# snare.net
KiCad netlist of a schematic drawn in EAGLE
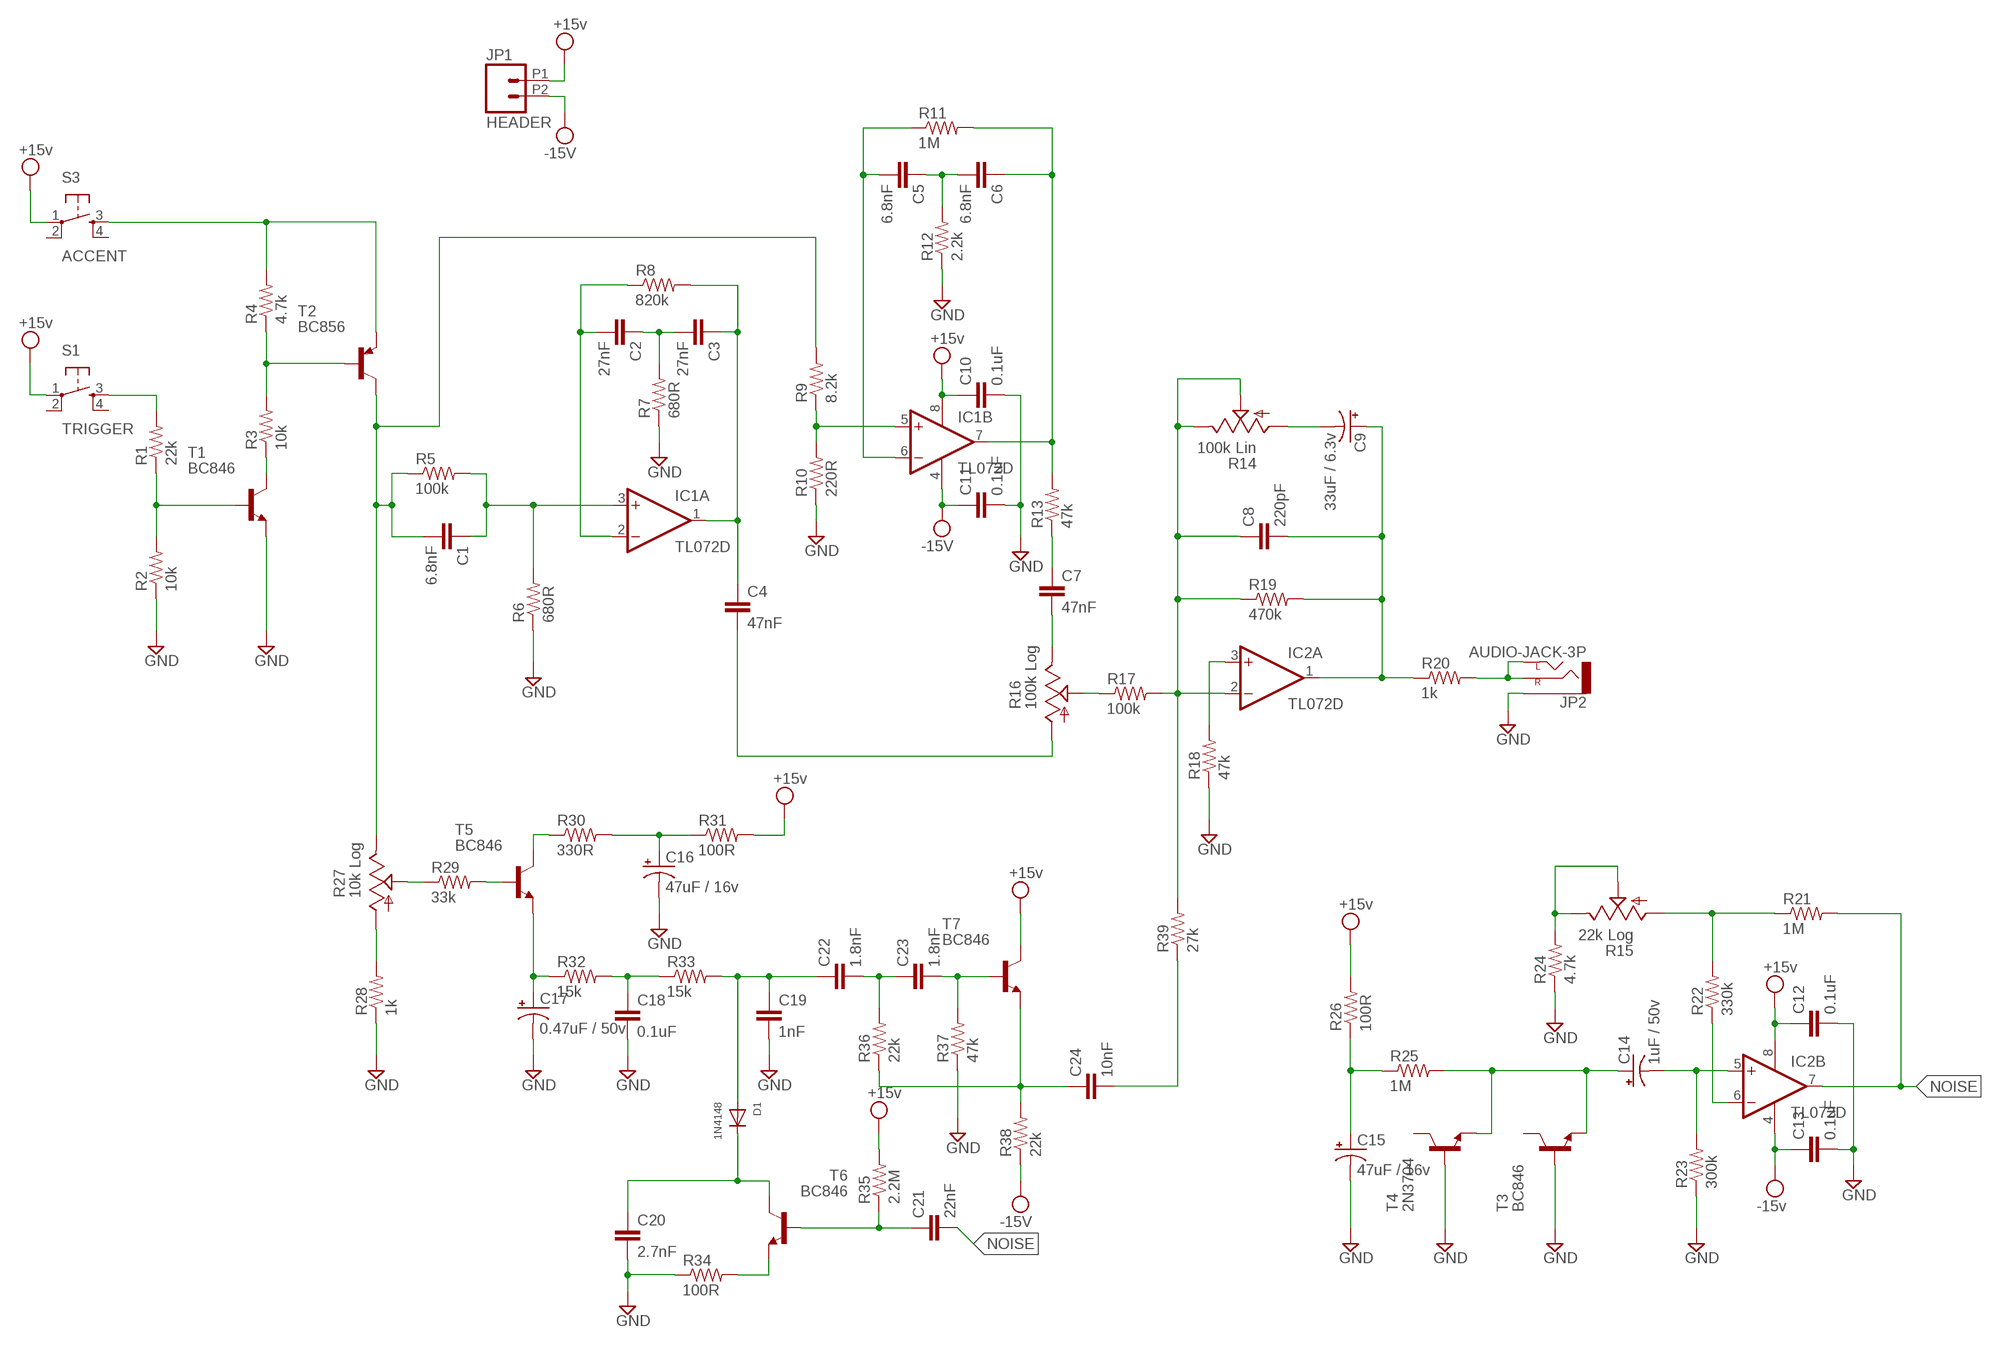
[diagram p0: schematic, sheet 1]

(export (version "E")
  (design (tool "Eeschema 10.0.6"))
  (components
    (comp (ref "C1")
      (value "6.8nF")
      (footprint "eagle-import:0805")
      (fields (field (name "PARTNO") "C0805C682K5RACTU"))
      (libsource (lib "eagle-import") (part "CAP0805"))
    )
    (comp (ref "C2")
      (value "27nF")
      (footprint "eagle-import:0805")
      (fields (field (name "PARTNO") "CC0805KRX7R9BB273"))
      (libsource (lib "eagle-import") (part "CAP0805"))
    )
    (comp (ref "C3")
      (value "27nF")
      (footprint "eagle-import:0805")
      (fields (field (name "PARTNO") "CC0805KRX7R9BB273"))
      (libsource (lib "eagle-import") (part "CAP0805"))
    )
    (comp (ref "C4")
      (value "47nF")
      (footprint "eagle-import:0805")
      (fields (field (name "PARTNO") "C0805C473K5RACTU"))
      (libsource (lib "eagle-import") (part "CAP0805"))
    )
    (comp (ref "C5")
      (value "6.8nF")
      (footprint "eagle-import:0805")
      (fields (field (name "PARTNO") "C0805C682K5RACTU"))
      (libsource (lib "eagle-import") (part "CAP0805"))
    )
    (comp (ref "C6")
      (value "6.8nF")
      (footprint "eagle-import:0805")
      (fields (field (name "PARTNO") "C0805C682K5RACTU"))
      (libsource (lib "eagle-import") (part "CAP0805"))
    )
    (comp (ref "C7")
      (value "47nF")
      (footprint "eagle-import:0805")
      (fields (field (name "PARTNO") "C0805C473K5RACTU"))
      (libsource (lib "eagle-import") (part "CAP0805"))
    )
    (comp (ref "C8")
      (value "220pF")
      (footprint "eagle-import:0805")
      (fields (field (name "PARTNO") "CC0805KRX7R9BB221"))
      (libsource (lib "eagle-import") (part "CAP0805"))
    )
    (comp (ref "C9")
      (value "33uF / 6.3v")
      (footprint "eagle-import:PANASONIC_VS_B-2")
      (fields (field (name "PARTNO") "EEE-1AA330WAR"))
      (libsource (lib "eagle-import") (part "CAP-POLPANASONIC_B-2"))
    )
    (comp (ref "C10")
      (value "0.1uF")
      (footprint "eagle-import:0805")
      (fields (field (name "PARTNO") "C0805C104K5RACTU"))
      (libsource (lib "eagle-import") (part "CAP0805"))
    )
    (comp (ref "C11")
      (value "0.1uF")
      (footprint "eagle-import:0805")
      (fields (field (name "PARTNO") "C0805C104K5RACTU"))
      (libsource (lib "eagle-import") (part "CAP0805"))
    )
    (comp (ref "C12")
      (value "0.1uF")
      (footprint "eagle-import:0805")
      (fields (field (name "PARTNO") "C0805C104K5RACTU"))
      (libsource (lib "eagle-import") (part "CAP0805"))
    )
    (comp (ref "C13")
      (value "0.1uF")
      (footprint "eagle-import:0805")
      (fields (field (name "PARTNO") "C0805C104K5RACTU"))
      (libsource (lib "eagle-import") (part "CAP0805"))
    )
    (comp (ref "C14")
      (value "1uF / 50v")
      (footprint "eagle-import:PANASONIC_VS_B-2")
      (fields (field (name "PARTNO") "EEE-1HA010SR"))
      (libsource (lib "eagle-import") (part "CAP-POLPANASONIC_B-2"))
    )
    (comp (ref "C15")
      (value "47uF / 16v")
      (footprint "eagle-import:PANASONIC_VS_B-2")
      (fields (field (name "PARTNO") "EEE-1HAR47AR"))
      (libsource (lib "eagle-import") (part "CAP-POLPANASONIC_B-2"))
    )
    (comp (ref "C16")
      (value "47uF / 16v")
      (footprint "eagle-import:PANASONIC_VS_B-2")
      (fields (field (name "PARTNO") "EEE-1HAR47AR"))
      (libsource (lib "eagle-import") (part "CAP-POLPANASONIC_B-2"))
    )
    (comp (ref "C17")
      (value "0.47uF / 50v")
      (footprint "eagle-import:PANASONIC_VS_B-2")
      (fields (field (name "PARTNO") "EEE-1HAR47AR"))
      (libsource (lib "eagle-import") (part "CAP-POLPANASONIC_B-2"))
    )
    (comp (ref "C18")
      (value "0.1uF")
      (footprint "eagle-import:0805")
      (fields (field (name "PARTNO") "C0805C104K5RACTU"))
      (libsource (lib "eagle-import") (part "CAP0805"))
    )
    (comp (ref "C19")
      (value "1nF")
      (footprint "eagle-import:0805")
      (fields (field (name "PARTNO") "C0805C102K5RACTU"))
      (libsource (lib "eagle-import") (part "CAP0805"))
    )
    (comp (ref "C20")
      (value "2.7nF")
      (footprint "eagle-import:0805")
      (fields (field (name "PARTNO") "CC0805KRX7R9BB272"))
      (libsource (lib "eagle-import") (part "CAP0805"))
    )
    (comp (ref "C21")
      (value "22nF")
      (footprint "eagle-import:0805")
      (fields (field (name "PARTNO") "CL21B223KBANNNC"))
      (libsource (lib "eagle-import") (part "CAP0805"))
    )
    (comp (ref "C22")
      (value "1.8nF")
      (footprint "eagle-import:0805")
      (fields (field (name "PARTNO") "08055C182KAT2A"))
      (libsource (lib "eagle-import") (part "CAP0805"))
    )
    (comp (ref "C23")
      (value "1.8nF")
      (footprint "eagle-import:0805")
      (fields (field (name "PARTNO") "08055C182KAT2A"))
      (libsource (lib "eagle-import") (part "CAP0805"))
    )
    (comp (ref "C24")
      (value "10nF")
      (footprint "eagle-import:0805")
      (fields (field (name "PARTNO") "GRM216R71H103KA01D"))
      (libsource (lib "eagle-import") (part "CAP0805"))
    )
    (comp (ref "D1")
      (value "1N4148")
      (footprint "eagle-import:SOD-323F")
      (fields (field (name "PARTNO") "1N4148WS"))
      (libsource (lib "eagle-import") (part "DIODESOD-323F"))
    )
    (comp (ref "IC1")
      (value "TL072D")
      (footprint "eagle-import:SO08")
      (fields (field (name "PARTNO") "TL072SG-13"))
      (libsource (lib "eagle-import") (part "TL072D"))
    )
    (comp (ref "IC2")
      (value "TL072D")
      (footprint "eagle-import:SO08")
      (fields (field (name "PARTNO") "TL072SG-13"))
      (libsource (lib "eagle-import") (part "TL072D"))
    )
    (comp (ref "JP1")
      (value "HEADER")
      (footprint "eagle-import:1X02-5.08-SCREWTERM")
      (libsource (lib "eagle-import") (part "HEADER"))
    )
    (comp (ref "JP2")
      (value "AUDIO-JACK-3P")
      (footprint "eagle-import:CUI-352X-SMT")
      (fields (field (name "PARTNO") "SJ-3523-SMT-TR"))
      (libsource (lib "eagle-import") (part "AUDIO-JACK-3P"))
    )
    (comp (ref "R1")
      (value "22k")
      (footprint "eagle-import:0805")
      (fields (field (name "PARTNO") "RMCF0805FT22K0"))
      (libsource (lib "eagle-import") (part "RESISTOR0805-RES"))
    )
    (comp (ref "R2")
      (value "10k")
      (footprint "eagle-import:0805")
      (fields (field (name "PARTNO") "RMCF0805FT10K0"))
      (libsource (lib "eagle-import") (part "RESISTOR0805-RES"))
    )
    (comp (ref "R3")
      (value "10k")
      (footprint "eagle-import:0805")
      (fields (field (name "PARTNO") "RMCF0805FT10K0"))
      (libsource (lib "eagle-import") (part "RESISTOR0805-RES"))
    )
    (comp (ref "R4")
      (value "4.7k")
      (footprint "eagle-import:0805")
      (fields (field (name "PARTNO") "RMCF0805FT4K70"))
      (libsource (lib "eagle-import") (part "RESISTOR0805-RES"))
    )
    (comp (ref "R5")
      (value "100k")
      (footprint "eagle-import:0805")
      (fields (field (name "PARTNO") "RMCF0805FT100K"))
      (libsource (lib "eagle-import") (part "RESISTOR0805-RES"))
    )
    (comp (ref "R6")
      (value "680R")
      (footprint "eagle-import:0805")
      (fields (field (name "PARTNO") "RMCF0805FT680R"))
      (libsource (lib "eagle-import") (part "RESISTOR0805-RES"))
    )
    (comp (ref "R7")
      (value "680R")
      (footprint "eagle-import:0805")
      (fields (field (name "PARTNO") "RMCF0805FT680R"))
      (libsource (lib "eagle-import") (part "RESISTOR0805-RES"))
    )
    (comp (ref "R8")
      (value "820k")
      (footprint "eagle-import:0805")
      (fields (field (name "PARTNO") "RC0805FR-07820KL"))
      (libsource (lib "eagle-import") (part "RESISTOR0805-RES"))
    )
    (comp (ref "R9")
      (value "8.2k")
      (footprint "eagle-import:0805")
      (fields (field (name "PARTNO") "RMCF0805FT8K20"))
      (libsource (lib "eagle-import") (part "RESISTOR0805-RES"))
    )
    (comp (ref "R10")
      (value "220R")
      (footprint "eagle-import:0805")
      (fields (field (name "PARTNO") "RMCF0805FT220R"))
      (libsource (lib "eagle-import") (part "RESISTOR0805-RES"))
    )
    (comp (ref "R11")
      (value "1M")
      (footprint "eagle-import:0805")
      (fields (field (name "PARTNO") "RMCF0805FT1M00"))
      (libsource (lib "eagle-import") (part "RESISTOR0805-RES"))
    )
    (comp (ref "R12")
      (value "2.2k")
      (footprint "eagle-import:0805")
      (fields (field (name "PARTNO") "RMCF0805FT2K20"))
      (libsource (lib "eagle-import") (part "RESISTOR0805-RES"))
    )
    (comp (ref "R13")
      (value "47k")
      (footprint "eagle-import:0805")
      (fields (field (name "PARTNO") "RMCF0805FT47K0"))
      (libsource (lib "eagle-import") (part "RESISTOR0805-RES"))
    )
    (comp (ref "R14")
      (value "100k Lin")
      (footprint "eagle-import:POTENTIOMETER-CTS296")
      (fields (field (name "PARTNO") "296UD104B1N"))
      (libsource (lib "eagle-import") (part "POTCTS296"))
    )
    (comp (ref "R15")
      (value "22k Log")
      (footprint "eagle-import:POTENTIOMETER-PTV09-HORIZ")
      (fields (field (name "PARTNO") "PTV09A-4025F-A203"))
      (libsource (lib "eagle-import") (part "POTPTV09-H"))
    )
    (comp (ref "R16")
      (value "100k Log")
      (footprint "eagle-import:POTENTIOMETER-PTV09-VERT")
      (fields (field (name "PARTNO") "PTV09A-2020F-A104"))
      (libsource (lib "eagle-import") (part "POTPTV09-V"))
    )
    (comp (ref "R17")
      (value "100k")
      (footprint "eagle-import:0805")
      (fields (field (name "PARTNO") "RMCF0805FT100K"))
      (libsource (lib "eagle-import") (part "RESISTOR0805-RES"))
    )
    (comp (ref "R18")
      (value "47k")
      (footprint "eagle-import:0805")
      (fields (field (name "PARTNO") "RMCF0805FT47K0"))
      (libsource (lib "eagle-import") (part "RESISTOR0805-RES"))
    )
    (comp (ref "R19")
      (value "470k")
      (footprint "eagle-import:0805")
      (fields (field (name "PARTNO") "CRCW0805470KFKEA"))
      (libsource (lib "eagle-import") (part "RESISTOR0805-RES"))
    )
    (comp (ref "R20")
      (value "1k")
      (footprint "eagle-import:0805")
      (fields (field (name "PARTNO") "RMCF0805FT1K00"))
      (libsource (lib "eagle-import") (part "RESISTOR0805-RES"))
    )
    (comp (ref "R21")
      (value "1M")
      (footprint "eagle-import:0805")
      (fields (field (name "PARTNO") "RMCF0805FT1M00"))
      (libsource (lib "eagle-import") (part "RESISTOR0805-RES"))
    )
    (comp (ref "R22")
      (value "330k")
      (footprint "eagle-import:0805")
      (fields (field (name "PARTNO") "RMCF0805FT330K"))
      (libsource (lib "eagle-import") (part "RESISTOR0805-RES"))
    )
    (comp (ref "R23")
      (value "300k")
      (footprint "eagle-import:0805")
      (fields (field (name "PARTNO") "RMCF0805FT300K"))
      (libsource (lib "eagle-import") (part "RESISTOR0805-RES"))
    )
    (comp (ref "R24")
      (value "4.7k")
      (footprint "eagle-import:0805")
      (fields (field (name "PARTNO") "RMCF0805FT4K70"))
      (libsource (lib "eagle-import") (part "RESISTOR0805-RES"))
    )
    (comp (ref "R25")
      (value "1M")
      (footprint "eagle-import:0805")
      (fields (field (name "PARTNO") "RMCF0805FT1M00"))
      (libsource (lib "eagle-import") (part "RESISTOR0805-RES"))
    )
    (comp (ref "R26")
      (value "100R")
      (footprint "eagle-import:0805")
      (fields (field (name "PARTNO") "RMCF0805FT100R"))
      (libsource (lib "eagle-import") (part "RESISTOR0805-RES"))
    )
    (comp (ref "R27")
      (value "10k Log")
      (footprint "eagle-import:POTENTIOMETER-PTV09-HORIZ")
      (fields (field (name "PARTNO") "PTV09A-4020F-A103"))
      (libsource (lib "eagle-import") (part "POTPTV09-H"))
    )
    (comp (ref "R28")
      (value "1k")
      (footprint "eagle-import:0805")
      (fields (field (name "PARTNO") "RMCF0805FT1K00"))
      (libsource (lib "eagle-import") (part "RESISTOR0805-RES"))
    )
    (comp (ref "R29")
      (value "33k")
      (footprint "eagle-import:0805")
      (fields (field (name "PARTNO") "RMCF0805FT33K0"))
      (libsource (lib "eagle-import") (part "RESISTOR0805-RES"))
    )
    (comp (ref "R30")
      (value "330R")
      (footprint "eagle-import:0805")
      (fields (field (name "PARTNO") "RMCF0805FT330R"))
      (libsource (lib "eagle-import") (part "RESISTOR0805-RES"))
    )
    (comp (ref "R31")
      (value "100R")
      (footprint "eagle-import:0805")
      (fields (field (name "PARTNO") "RMCF0805FT100R"))
      (libsource (lib "eagle-import") (part "RESISTOR0805-RES"))
    )
    (comp (ref "R32")
      (value "15k")
      (footprint "eagle-import:0805")
      (fields (field (name "PARTNO") "RMCF0805FT15K0"))
      (libsource (lib "eagle-import") (part "RESISTOR0805-RES"))
    )
    (comp (ref "R33")
      (value "15k")
      (footprint "eagle-import:0805")
      (fields (field (name "PARTNO") "RMCF0805FT15K0"))
      (libsource (lib "eagle-import") (part "RESISTOR0805-RES"))
    )
    (comp (ref "R34")
      (value "100R")
      (footprint "eagle-import:0805")
      (fields (field (name "PARTNO") "RMCF0805FT100R"))
      (libsource (lib "eagle-import") (part "RESISTOR0805-RES"))
    )
    (comp (ref "R35")
      (value "2.2M")
      (footprint "eagle-import:0805")
      (fields (field (name "PARTNO") "RC0805FR-072M2L"))
      (libsource (lib "eagle-import") (part "RESISTOR0805-RES"))
    )
    (comp (ref "R36")
      (value "22k")
      (footprint "eagle-import:0805")
      (fields (field (name "PARTNO") "RMCF0805FT22K0"))
      (libsource (lib "eagle-import") (part "RESISTOR0805-RES"))
    )
    (comp (ref "R37")
      (value "47k")
      (footprint "eagle-import:0805")
      (fields (field (name "PARTNO") "RMCF0805FT47K0"))
      (libsource (lib "eagle-import") (part "RESISTOR0805-RES"))
    )
    (comp (ref "R38")
      (value "22k")
      (footprint "eagle-import:0805")
      (fields (field (name "PARTNO") "RMCF0805FT22K0"))
      (libsource (lib "eagle-import") (part "RESISTOR0805-RES"))
    )
    (comp (ref "R39")
      (value "27k")
      (footprint "eagle-import:0805")
      (fields (field (name "PARTNO") "RMCF0805FT27K0"))
      (libsource (lib "eagle-import") (part "RESISTOR0805-RES"))
    )
    (comp (ref "S1")
      (value "TRIGGER")
      (footprint "eagle-import:TACTILE_SWITCH_SMD")
      (fields (field (name "PARTNO") "PTS525SM10SMTR LFS"))
      (libsource (lib "eagle-import") (part "TAC_SWITCHSMD"))
    )
    (comp (ref "S3")
      (value "ACCENT")
      (footprint "eagle-import:TACTILE_SWITCH_SMD")
      (fields (field (name "PARTNO") "PTS525SM10SMTR LFS"))
      (libsource (lib "eagle-import") (part "TAC_SWITCHSMD"))
    )
    (comp (ref "T1")
      (value "BC846")
      (footprint "eagle-import:SOT23")
      (fields (field (name "PARTNO") "BC846BMTF"))
      (libsource (lib "eagle-import") (part "BC846"))
    )
    (comp (ref "T2")
      (value "BC856")
      (footprint "eagle-import:SOT23-BEC")
      (fields (field (name "PARTNO") "BC856BMTF"))
      (libsource (lib "eagle-import") (part "-PNP-SOT23-BECBC856B"))
    )
    (comp (ref "T3")
      (value "BC846")
      (footprint "eagle-import:SOT23")
      (fields (field (name "PARTNO") "BC846BMTF"))
      (libsource (lib "eagle-import") (part "BC846"))
    )
    (comp (ref "T4")
      (value "2N3704")
      (footprint "eagle-import:TO92")
      (libsource (lib "eagle-import") (part "2N3704"))
    )
    (comp (ref "T5")
      (value "BC846")
      (footprint "eagle-import:SOT23")
      (fields (field (name "PARTNO") "BC846BMTF"))
      (libsource (lib "eagle-import") (part "BC846"))
    )
    (comp (ref "T6")
      (value "BC846")
      (footprint "eagle-import:SOT23")
      (fields (field (name "PARTNO") "BC846BMTF"))
      (libsource (lib "eagle-import") (part "BC846"))
    )
    (comp (ref "T7")
      (value "BC846")
      (footprint "eagle-import:SOT23")
      (fields (field (name "PARTNO") "BC846BMTF"))
      (libsource (lib "eagle-import") (part "BC846"))
    )
  )
  (nets
    (net (code "1") (name "+15v") (class "Default")
      (node (ref "C10") (pin "1") (pinfunction "1_1") (pintype "passive"))
      (node (ref "C12") (pin "1") (pinfunction "1_1") (pintype "passive"))
      (node (ref "IC1") (pin "8") (pinfunction "V+_8") (pintype "power_in"))
      (node (ref "IC2") (pin "8") (pinfunction "V+_8") (pintype "power_in"))
      (node (ref "JP1") (pin "P1") (pinfunction "2_P1") (pintype "passive"))
      (node (ref "R26") (pin "2") (pinfunction "2_2") (pintype "passive"))
      (node (ref "R31") (pin "2") (pinfunction "2_2") (pintype "passive"))
      (node (ref "R35") (pin "2") (pinfunction "2_2") (pintype "passive"))
      (node (ref "S1") (pin "1") (pinfunction "1_1") (pintype "passive"))
      (node (ref "S3") (pin "1") (pinfunction "1_1") (pintype "passive"))
      (node (ref "T7") (pin "3") (pinfunction "C_3") (pintype "passive"))
    )
    (net (code "2") (name "-15V") (class "Default")
      (node (ref "C11") (pin "1") (pinfunction "1_1") (pintype "passive"))
      (node (ref "C13") (pin "1") (pinfunction "1_1") (pintype "passive"))
      (node (ref "IC1") (pin "4") (pinfunction "V-_4") (pintype "power_in"))
      (node (ref "IC2") (pin "4") (pinfunction "V-_4") (pintype "power_in"))
      (node (ref "JP1") (pin "P2") (pinfunction "1_P2") (pintype "passive"))
      (node (ref "R38") (pin "1") (pinfunction "1_1") (pintype "passive"))
    )
    (net (code "3") (name "GND") (class "Default")
      (node (ref "C10") (pin "2") (pinfunction "2_2") (pintype "passive"))
      (node (ref "C11") (pin "2") (pinfunction "2_2") (pintype "passive"))
      (node (ref "C12") (pin "2") (pinfunction "2_2") (pintype "passive"))
      (node (ref "C13") (pin "2") (pinfunction "2_2") (pintype "passive"))
      (node (ref "C15") (pin "-") (pinfunction "-_-") (pintype "passive"))
      (node (ref "C16") (pin "-") (pinfunction "-_-") (pintype "passive"))
      (node (ref "C17") (pin "-") (pinfunction "-_-") (pintype "passive"))
      (node (ref "C18") (pin "2") (pinfunction "2_2") (pintype "passive"))
      (node (ref "C19") (pin "2") (pinfunction "2_2") (pintype "passive"))
      (node (ref "C20") (pin "2") (pinfunction "2_2") (pintype "passive"))
      (node (ref "JP2") (pin "1") (pinfunction "SLEEVE_1") (pintype "bidirectional"))
      (node (ref "R10") (pin "1") (pinfunction "1_1") (pintype "passive"))
      (node (ref "R12") (pin "1") (pinfunction "1_1") (pintype "passive"))
      (node (ref "R18") (pin "1") (pinfunction "1_1") (pintype "passive"))
      (node (ref "R2") (pin "1") (pinfunction "1_1") (pintype "passive"))
      (node (ref "R23") (pin "1") (pinfunction "1_1") (pintype "passive"))
      (node (ref "R24") (pin "1") (pinfunction "1_1") (pintype "passive"))
      (node (ref "R28") (pin "1") (pinfunction "1_1") (pintype "passive"))
      (node (ref "R34") (pin "1") (pinfunction "1_1") (pintype "passive"))
      (node (ref "R37") (pin "1") (pinfunction "1_1") (pintype "passive"))
      (node (ref "R6") (pin "1") (pinfunction "1_1") (pintype "passive"))
      (node (ref "R7") (pin "1") (pinfunction "1_1") (pintype "passive"))
      (node (ref "T1") (pin "2") (pinfunction "E_2") (pintype "passive"))
      (node (ref "T3") (pin "1") (pinfunction "B_1") (pintype "passive"))
      (node (ref "T4") (pin "1") (pinfunction "B_1") (pintype "passive"))
    )
    (net (code "4") (name "NOISE") (class "Default")
      (node (ref "C21") (pin "2") (pinfunction "2_2") (pintype "passive"))
      (node (ref "IC2") (pin "7") (pinfunction "OUT_7") (pintype "output"))
      (node (ref "R21") (pin "2") (pinfunction "2_2") (pintype "passive"))
    )
    (net (code "5") (name "Net-(C2-Pad1)") (class "Default")
      (node (ref "C2") (pin "1") (pinfunction "1_1") (pintype "passive"))
      (node (ref "C3") (pin "2") (pinfunction "2_2") (pintype "passive"))
      (node (ref "R7") (pin "2") (pinfunction "2_2") (pintype "passive"))
    )
    (net (code "6") (name "Net-(C5-Pad1)") (class "Default")
      (node (ref "C5") (pin "1") (pinfunction "1_1") (pintype "passive"))
      (node (ref "C6") (pin "2") (pinfunction "2_2") (pintype "passive"))
      (node (ref "R12") (pin "2") (pinfunction "2_2") (pintype "passive"))
    )
    (net (code "7") (name "Net-(C7-Pad1)") (class "Default")
      (node (ref "C7") (pin "1") (pinfunction "1_1") (pintype "passive"))
      (node (ref "R13") (pin "1") (pinfunction "1_1") (pintype "passive"))
    )
    (net (code "8") (name "Net-(C15-Pad+)") (class "Default")
      (node (ref "C15") (pin "+") (pinfunction "+_+") (pintype "passive"))
      (node (ref "R25") (pin "1") (pinfunction "1_1") (pintype "passive"))
      (node (ref "R26") (pin "1") (pinfunction "1_1") (pintype "passive"))
    )
    (net (code "9") (name "Net-(C16-Pad+)") (class "Default")
      (node (ref "C16") (pin "+") (pinfunction "+_+") (pintype "passive"))
      (node (ref "R30") (pin "2") (pinfunction "2_2") (pintype "passive"))
      (node (ref "R31") (pin "1") (pinfunction "1_1") (pintype "passive"))
    )
    (net (code "10") (name "Net-(C18-Pad1)") (class "Default")
      (node (ref "C18") (pin "1") (pinfunction "1_1") (pintype "passive"))
      (node (ref "R32") (pin "2") (pinfunction "2_2") (pintype "passive"))
      (node (ref "R33") (pin "1") (pinfunction "1_1") (pintype "passive"))
    )
    (net (code "11") (name "Net-(C19-Pad1)") (class "Default")
      (node (ref "C19") (pin "1") (pinfunction "1_1") (pintype "passive"))
      (node (ref "C22") (pin "1") (pinfunction "1_1") (pintype "passive"))
      (node (ref "D1") (pin "A") (pinfunction "A_A") (pintype "passive"))
      (node (ref "R33") (pin "2") (pinfunction "2_2") (pintype "passive"))
    )
    (net (code "12") (name "Net-(C22-Pad2)") (class "Default")
      (node (ref "C22") (pin "2") (pinfunction "2_2") (pintype "passive"))
      (node (ref "C23") (pin "1") (pinfunction "1_1") (pintype "passive"))
      (node (ref "R36") (pin "2") (pinfunction "2_2") (pintype "passive"))
    )
    (net (code "13") (name "Net-(C24-Pad2)") (class "Default")
      (node (ref "C24") (pin "2") (pinfunction "2_2") (pintype "passive"))
      (node (ref "R39") (pin "1") (pinfunction "1_1") (pintype "passive"))
    )
    (net (code "14") (name "Net-(IC1A-+IN)") (class "Default")
      (node (ref "C1") (pin "1") (pinfunction "1_1") (pintype "passive"))
      (node (ref "IC1") (pin "3") (pinfunction "+IN_3") (pintype "input"))
      (node (ref "R5") (pin "2") (pinfunction "2_2") (pintype "passive"))
      (node (ref "R6") (pin "2") (pinfunction "2_2") (pintype "passive"))
    )
    (net (code "15") (name "Net-(IC1A--IN)") (class "Default")
      (node (ref "C2") (pin "2") (pinfunction "2_2") (pintype "passive"))
      (node (ref "IC1") (pin "2") (pinfunction "-IN_2") (pintype "input"))
      (node (ref "R8") (pin "1") (pinfunction "1_1") (pintype "passive"))
    )
    (net (code "16") (name "Net-(IC1A-OUT)") (class "Default")
      (node (ref "C3") (pin "1") (pinfunction "1_1") (pintype "passive"))
      (node (ref "C4") (pin "1") (pinfunction "1_1") (pintype "passive"))
      (node (ref "IC1") (pin "1") (pinfunction "OUT_1") (pintype "output"))
      (node (ref "R8") (pin "2") (pinfunction "2_2") (pintype "passive"))
    )
    (net (code "17") (name "Net-(IC1B-+IN)") (class "Default")
      (node (ref "IC1") (pin "5") (pinfunction "+IN_5") (pintype "input"))
      (node (ref "R10") (pin "2") (pinfunction "2_2") (pintype "passive"))
      (node (ref "R9") (pin "1") (pinfunction "1_1") (pintype "passive"))
    )
    (net (code "18") (name "Net-(IC1B--IN)") (class "Default")
      (node (ref "C5") (pin "2") (pinfunction "2_2") (pintype "passive"))
      (node (ref "IC1") (pin "6") (pinfunction "-IN_6") (pintype "input"))
      (node (ref "R11") (pin "1") (pinfunction "1_1") (pintype "passive"))
    )
    (net (code "19") (name "Net-(IC1B-OUT)") (class "Default")
      (node (ref "C6") (pin "1") (pinfunction "1_1") (pintype "passive"))
      (node (ref "IC1") (pin "7") (pinfunction "OUT_7") (pintype "output"))
      (node (ref "R11") (pin "2") (pinfunction "2_2") (pintype "passive"))
      (node (ref "R13") (pin "2") (pinfunction "2_2") (pintype "passive"))
    )
    (net (code "20") (name "Net-(IC2A-+IN)") (class "Default")
      (node (ref "IC2") (pin "3") (pinfunction "+IN_3") (pintype "input"))
      (node (ref "R18") (pin "2") (pinfunction "2_2") (pintype "passive"))
    )
    (net (code "21") (name "Net-(IC2A--IN)") (class "Default")
      (node (ref "C8") (pin "1") (pinfunction "1_1") (pintype "passive"))
      (node (ref "IC2") (pin "2") (pinfunction "-IN_2") (pintype "input"))
      (node (ref "R14") (pin "P$2") (pinfunction "S_P$2") (pintype "passive"))
      (node (ref "R14") (pin "P$3") (pinfunction "E_P$3") (pintype "passive"))
      (node (ref "R17") (pin "2") (pinfunction "2_2") (pintype "passive"))
      (node (ref "R19") (pin "1") (pinfunction "1_1") (pintype "passive"))
      (node (ref "R39") (pin "2") (pinfunction "2_2") (pintype "passive"))
    )
    (net (code "22") (name "Net-(IC2A-OUT)") (class "Default")
      (node (ref "C8") (pin "2") (pinfunction "2_2") (pintype "passive"))
      (node (ref "C9") (pin "+") (pinfunction "+_+") (pintype "passive"))
      (node (ref "IC2") (pin "1") (pinfunction "OUT_1") (pintype "output"))
      (node (ref "R19") (pin "2") (pinfunction "2_2") (pintype "passive"))
      (node (ref "R20") (pin "1") (pinfunction "1_1") (pintype "passive"))
    )
    (net (code "23") (name "Net-(IC2B-+IN)") (class "Default")
      (node (ref "C14") (pin "-") (pinfunction "-_-") (pintype "passive"))
      (node (ref "IC2") (pin "5") (pinfunction "+IN_5") (pintype "input"))
      (node (ref "R23") (pin "2") (pinfunction "2_2") (pintype "passive"))
    )
    (net (code "24") (name "Net-(IC2B--IN)") (class "Default")
      (node (ref "IC2") (pin "6") (pinfunction "-IN_6") (pintype "input"))
      (node (ref "R22") (pin "1") (pinfunction "1_1") (pintype "passive"))
    )
    (net (code "25") (name "Net-(JP2-LEFT)") (class "Default")
      (node (ref "JP2") (pin "2") (pinfunction "LEFT_2") (pintype "bidirectional"))
      (node (ref "JP2") (pin "3") (pinfunction "RIGHT_3") (pintype "bidirectional"))
      (node (ref "R20") (pin "2") (pinfunction "2_2") (pintype "passive"))
    )
    (net (code "26") (name "Net-(R1-Pad2)") (class "Default")
      (node (ref "R1") (pin "2") (pinfunction "2_2") (pintype "passive"))
      (node (ref "S1") (pin "3") (pinfunction "3_3") (pintype "passive"))
    )
    (net (code "27") (name "Net-(R3-Pad2)") (class "Default")
      (node (ref "R3") (pin "2") (pinfunction "2_2") (pintype "passive"))
      (node (ref "R4") (pin "1") (pinfunction "1_1") (pintype "passive"))
      (node (ref "T2") (pin "B") (pinfunction "B_B") (pintype "passive"))
    )
    (net (code "28") (name "Net-(R4-Pad2)") (class "Default")
      (node (ref "R4") (pin "2") (pinfunction "2_2") (pintype "passive"))
      (node (ref "S3") (pin "3") (pinfunction "3_3") (pintype "passive"))
      (node (ref "T2") (pin "E") (pinfunction "E_E") (pintype "passive"))
    )
    (net (code "29") (name "Net-(R14-A)") (class "Default")
      (node (ref "C9") (pin "-") (pinfunction "-_-") (pintype "passive"))
      (node (ref "R14") (pin "P$1") (pinfunction "A_P$1") (pintype "passive"))
    )
    (net (code "30") (name "Net-(R15-A)") (class "Default")
      (node (ref "R15") (pin "P$1") (pinfunction "A_P$1") (pintype "passive"))
      (node (ref "R21") (pin "1") (pinfunction "1_1") (pintype "passive"))
      (node (ref "R22") (pin "2") (pinfunction "2_2") (pintype "passive"))
    )
    (net (code "31") (name "Net-(R15-E)") (class "Default")
      (node (ref "R15") (pin "P$2") (pinfunction "S_P$2") (pintype "passive"))
      (node (ref "R15") (pin "P$3") (pinfunction "E_P$3") (pintype "passive"))
      (node (ref "R24") (pin "2") (pinfunction "2_2") (pintype "passive"))
    )
    (net (code "32") (name "Net-(R16-A)") (class "Default")
      (node (ref "C4") (pin "2") (pinfunction "2_2") (pintype "passive"))
      (node (ref "R16") (pin "P$1") (pinfunction "A_P$1") (pintype "passive"))
    )
    (net (code "33") (name "Net-(R16-E)") (class "Default")
      (node (ref "C7") (pin "2") (pinfunction "2_2") (pintype "passive"))
      (node (ref "R16") (pin "P$3") (pinfunction "E_P$3") (pintype "passive"))
    )
    (net (code "34") (name "Net-(R16-S)") (class "Default")
      (node (ref "R16") (pin "P$2") (pinfunction "S_P$2") (pintype "passive"))
      (node (ref "R17") (pin "1") (pinfunction "1_1") (pintype "passive"))
    )
    (net (code "35") (name "Net-(R27-A)") (class "Default")
      (node (ref "R27") (pin "P$1") (pinfunction "A_P$1") (pintype "passive"))
      (node (ref "R28") (pin "2") (pinfunction "2_2") (pintype "passive"))
    )
    (net (code "36") (name "Net-(R27-E)") (class "Default")
      (node (ref "C1") (pin "2") (pinfunction "2_2") (pintype "passive"))
      (node (ref "R27") (pin "P$3") (pinfunction "E_P$3") (pintype "passive"))
      (node (ref "R5") (pin "1") (pinfunction "1_1") (pintype "passive"))
      (node (ref "R9") (pin "2") (pinfunction "2_2") (pintype "passive"))
      (node (ref "T2") (pin "C") (pinfunction "C_C") (pintype "passive"))
    )
    (net (code "37") (name "Net-(R27-S)") (class "Default")
      (node (ref "R27") (pin "P$2") (pinfunction "S_P$2") (pintype "passive"))
      (node (ref "R29") (pin "1") (pinfunction "1_1") (pintype "passive"))
    )
    (net (code "38") (name "Net-(T1-B)") (class "Default")
      (node (ref "R1") (pin "1") (pinfunction "1_1") (pintype "passive"))
      (node (ref "R2") (pin "2") (pinfunction "2_2") (pintype "passive"))
      (node (ref "T1") (pin "1") (pinfunction "B_1") (pintype "passive"))
    )
    (net (code "39") (name "Net-(T1-C)") (class "Default")
      (node (ref "R3") (pin "1") (pinfunction "1_1") (pintype "passive"))
      (node (ref "T1") (pin "3") (pinfunction "C_3") (pintype "passive"))
    )
    (net (code "40") (name "Net-(T3-E)") (class "Default")
      (node (ref "C14") (pin "+") (pinfunction "+_+") (pintype "passive"))
      (node (ref "R25") (pin "2") (pinfunction "2_2") (pintype "passive"))
      (node (ref "T3") (pin "2") (pinfunction "E_2") (pintype "passive"))
      (node (ref "T4") (pin "3") (pinfunction "E_3") (pintype "passive"))
    )
    (net (code "41") (name "Net-(T5-B)") (class "Default")
      (node (ref "R29") (pin "2") (pinfunction "2_2") (pintype "passive"))
      (node (ref "T5") (pin "1") (pinfunction "B_1") (pintype "passive"))
    )
    (net (code "42") (name "Net-(T5-C)") (class "Default")
      (node (ref "R30") (pin "1") (pinfunction "1_1") (pintype "passive"))
      (node (ref "T5") (pin "3") (pinfunction "C_3") (pintype "passive"))
    )
    (net (code "43") (name "Net-(T5-E)") (class "Default")
      (node (ref "C17") (pin "+") (pinfunction "+_+") (pintype "passive"))
      (node (ref "R32") (pin "1") (pinfunction "1_1") (pintype "passive"))
      (node (ref "T5") (pin "2") (pinfunction "E_2") (pintype "passive"))
    )
    (net (code "44") (name "Net-(T6-B)") (class "Default")
      (node (ref "C21") (pin "1") (pinfunction "1_1") (pintype "passive"))
      (node (ref "R35") (pin "1") (pinfunction "1_1") (pintype "passive"))
      (node (ref "T6") (pin "1") (pinfunction "B_1") (pintype "passive"))
    )
    (net (code "45") (name "Net-(T6-C)") (class "Default")
      (node (ref "C20") (pin "1") (pinfunction "1_1") (pintype "passive"))
      (node (ref "D1") (pin "C") (pinfunction "C_C") (pintype "passive"))
      (node (ref "T6") (pin "3") (pinfunction "C_3") (pintype "passive"))
    )
    (net (code "46") (name "Net-(T6-E)") (class "Default")
      (node (ref "R34") (pin "2") (pinfunction "2_2") (pintype "passive"))
      (node (ref "T6") (pin "2") (pinfunction "E_2") (pintype "passive"))
    )
    (net (code "47") (name "Net-(T7-B)") (class "Default")
      (node (ref "C23") (pin "2") (pinfunction "2_2") (pintype "passive"))
      (node (ref "R37") (pin "2") (pinfunction "2_2") (pintype "passive"))
      (node (ref "T7") (pin "1") (pinfunction "B_1") (pintype "passive"))
    )
    (net (code "48") (name "Net-(T7-E)") (class "Default")
      (node (ref "C24") (pin "1") (pinfunction "1_1") (pintype "passive"))
      (node (ref "R36") (pin "1") (pinfunction "1_1") (pintype "passive"))
      (node (ref "R38") (pin "2") (pinfunction "2_2") (pintype "passive"))
      (node (ref "T7") (pin "2") (pinfunction "E_2") (pintype "passive"))
    )
    (net (code "49") (name "unconnected-(S1-Pad2)") (class "Default")
      (node (ref "S1") (pin "2") (pinfunction "2_2") (pintype "passive"))
    )
    (net (code "50") (name "unconnected-(S1-Pad4)") (class "Default")
      (node (ref "S1") (pin "4") (pinfunction "4_4") (pintype "passive"))
    )
    (net (code "51") (name "unconnected-(S3-Pad2)") (class "Default")
      (node (ref "S3") (pin "2") (pinfunction "2_2") (pintype "passive"))
    )
    (net (code "52") (name "unconnected-(S3-Pad4)") (class "Default")
      (node (ref "S3") (pin "4") (pinfunction "4_4") (pintype "passive"))
    )
    (net (code "53") (name "unconnected-(T3-C-Pad3)") (class "Default")
      (node (ref "T3") (pin "3") (pinfunction "C_3") (pintype "passive"))
    )
    (net (code "54") (name "unconnected-(T4-C-Pad2)") (class "Default")
      (node (ref "T4") (pin "2") (pinfunction "C_2") (pintype "passive"))
    )
  )
)
